# Sheet1.net
KiCad netlist of a schematic drawn in Altium Designer
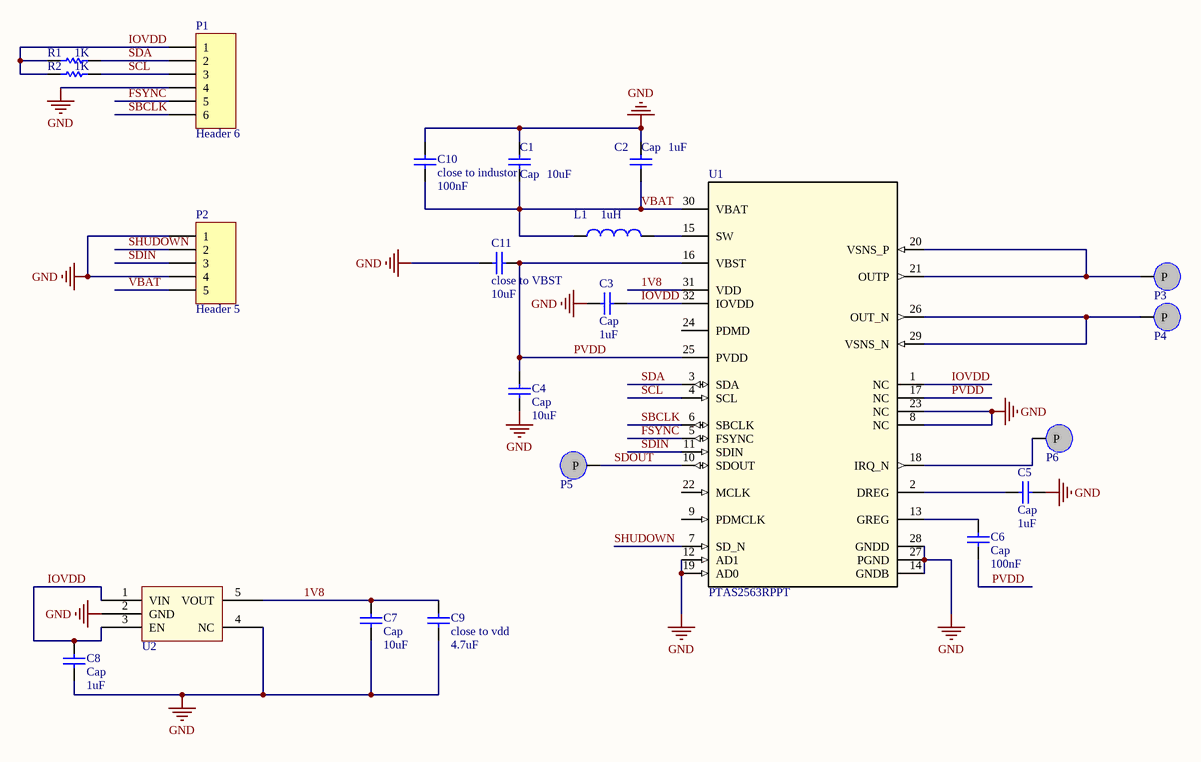
[diagram p0: Sheet1.SchDoc]

(export (version "E")
  (design (tool "Eeschema 10.0.6"))
  (components
    (comp (ref "C1")
      (value "Cap")
      (footprint "6-0805_L")
      (description "Capacitor")
      (fields (field (name "ALTIUM_VALUE") "10uF") (field (name "PUBLISHER") "Altium Limited"))
      (libsource (lib "Miscellaneous Devices") (part "Cap"))
    )
    (comp (ref "C2")
      (value "Cap")
      (footprint "6-0805_L")
      (description "Capacitor")
      (fields (field (name "ALTIUM_VALUE") "1uF") (field (name "PUBLISHER") "Altium Limited"))
      (libsource (lib "Miscellaneous Devices") (part "Cap"))
    )
    (comp (ref "C3")
      (value "Cap")
      (footprint "6-0805_L")
      (description "Capacitor")
      (fields (field (name "ALTIUM_VALUE") "1uF") (field (name "PUBLISHER") "Altium Limited"))
      (libsource (lib "Miscellaneous Devices") (part "Cap"))
    )
    (comp (ref "C4")
      (value "Cap")
      (footprint "6-0805_L")
      (description "Capacitor")
      (fields (field (name "ALTIUM_VALUE") "10uF") (field (name "PUBLISHER") "Altium Limited"))
      (libsource (lib "Miscellaneous Devices") (part "Cap"))
    )
    (comp (ref "C5")
      (value "Cap")
      (footprint "6-0805_L")
      (description "Capacitor")
      (fields (field (name "ALTIUM_VALUE") "1uF") (field (name "PUBLISHER") "Altium Limited"))
      (libsource (lib "Miscellaneous Devices") (part "Cap"))
    )
    (comp (ref "C6")
      (value "Cap")
      (footprint "1608[0603]")
      (description "Capacitor")
      (fields (field (name "ALTIUM_VALUE") "100nF") (field (name "PUBLISHER") "Altium Limited"))
      (libsource (lib "Miscellaneous Devices") (part "Cap"))
    )
    (comp (ref "C7")
      (value "Cap")
      (footprint "6-0805_L")
      (description "Capacitor")
      (fields (field (name "ALTIUM_VALUE") "10uF") (field (name "PUBLISHER") "Altium Limited"))
      (libsource (lib "Miscellaneous Devices") (part "Cap"))
    )
    (comp (ref "C8")
      (value "Cap")
      (footprint "6-0805_L")
      (description "Capacitor")
      (fields (field (name "ALTIUM_VALUE") "1uF") (field (name "PUBLISHER") "Altium Limited"))
      (libsource (lib "Miscellaneous Devices") (part "Cap"))
    )
    (comp (ref "C9")
      (value "close to vdd")
      (footprint "6-0805_L")
      (description "Capacitor")
      (fields (field (name "ALTIUM_VALUE") "4.7uF") (field (name "PUBLISHER") "Altium Limited"))
      (libsource (lib "Miscellaneous Devices") (part "Cap"))
    )
    (comp (ref "C10")
      (value "close to industor")
      (footprint "0402")
      (description "Capacitor")
      (fields (field (name "ALTIUM_VALUE") "100nF") (field (name "PUBLISHER") "Altium Limited"))
      (libsource (lib "Miscellaneous Devices") (part "Cap"))
    )
    (comp (ref "C11")
      (value "close to VBST")
      (footprint "6-0805_L")
      (description "Capacitor")
      (fields (field (name "ALTIUM_VALUE") "10uF") (field (name "PUBLISHER") "Altium Limited"))
      (libsource (lib "Miscellaneous Devices") (part "Cap"))
    )
    (comp (ref "L1")
      (value "1uH")
      (footprint "4040X20L")
      (description "Inductor")
      (fields (field (name "PUBLISHER") "Altium Limited"))
      (libsource (lib "Miscellaneous Devices") (part "Inductor"))
    )
    (comp (ref "P1")
      (value "Header 6")
      (footprint "DIP6-HOLE")
      (description "Header, 6-Pin")
      (fields (field (name "PUBLISHER") "Altium Limited"))
      (libsource (lib "Miscellaneous Connectors") (part "Header 6"))
    )
    (comp (ref "P2")
      (value "Header 5")
      (footprint "DIP5-HOLE")
      (description "Header, 5-Pin")
      (fields (field (name "PUBLISHER") "Altium Limited"))
      (libsource (lib "Miscellaneous Connectors") (part "Header 5"))
    )
    (comp (ref "P3") (value "Point") (footprint "Point") (libsource (lib "cl_sch") (part "Point")))
    (comp (ref "P4") (value "Point") (footprint "Point") (libsource (lib "cl_sch") (part "Point")))
    (comp (ref "P5") (value "Point") (footprint "Point-min") (libsource (lib "cl_sch") (part "Point")))
    (comp (ref "P6") (value "Point") (footprint "Point-min") (libsource (lib "cl_sch") (part "Point")))
    (comp (ref "R1")
      (value "1K")
      (footprint "0402")
      (description "Resistor")
      (fields (field (name "Comment") "Res1") (field (name "PUBLISHER") "Altium Limited"))
      (libsource (lib "Miscellaneous Devices") (part "Res1"))
    )
    (comp (ref "R2")
      (value "1K")
      (footprint "0402")
      (description "Resistor")
      (fields (field (name "Comment") "Res1") (field (name "PUBLISHER") "Altium Limited"))
      (libsource (lib "Miscellaneous Devices") (part "Res1"))
    )
    (comp (ref "U1")
      (value "PTAS2563RPPT")
      (footprint "RPP0032B-MFG")
      (description "No Description Available")
      (fields (field (name "COPYRIGHT") "Copyright (C) 2023 Ultra Librarian. All rights reserved."))
      (libsource (lib "PTAS2563RPPT") (part "PTAS2563RPPT"))
    )
    (comp (ref "U2") (value "TPS70918") (footprint "SOT23-5") (libsource (lib "cl_sch") (part "TPS70918")))
  )
  (nets
    (net (code "1") (name "/1V8") (class "Default")
      (node (ref "C7") (pin "2") (pinfunction "2_2") (pintype "passive"))
      (node (ref "C9") (pin "2") (pinfunction "2_2") (pintype "passive"))
      (node (ref "U1") (pin "31") (pinfunction "VDD_31") (pintype "power_in"))
      (node (ref "U2") (pin "5") (pinfunction "VOUT_5") (pintype "passive"))
    )
    (net (code "2") (name "/FSYNC") (class "Default")
      (node (ref "P1") (pin "5") (pinfunction "5_5") (pintype "passive"))
      (node (ref "U1") (pin "5") (pinfunction "FSYNC_5") (pintype "bidirectional"))
    )
    (net (code "3") (name "/IOVDD") (class "Default")
      (node (ref "C3") (pin "1") (pinfunction "1_1") (pintype "passive"))
      (node (ref "C8") (pin "2") (pinfunction "2_2") (pintype "passive"))
      (node (ref "P1") (pin "1") (pinfunction "1_1") (pintype "passive"))
      (node (ref "R1") (pin "1") (pinfunction "1_1") (pintype "passive"))
      (node (ref "R2") (pin "1") (pinfunction "1_1") (pintype "passive"))
      (node (ref "U1") (pin "1") (pinfunction "NC_1") (pintype "passive"))
      (node (ref "U1") (pin "32") (pinfunction "IOVDD_32") (pintype "power_in"))
      (node (ref "U2") (pin "1") (pinfunction "VIN_1") (pintype "passive"))
      (node (ref "U2") (pin "3") (pinfunction "EN_3") (pintype "passive"))
    )
    (net (code "4") (name "/PVDD") (class "Default")
      (node (ref "C11") (pin "1") (pinfunction "1_1") (pintype "passive"))
      (node (ref "C4") (pin "2") (pinfunction "2_2") (pintype "passive"))
      (node (ref "C6") (pin "2") (pinfunction "2_2") (pintype "passive"))
      (node (ref "U1") (pin "16") (pinfunction "VBST_16") (pintype "power_in"))
      (node (ref "U1") (pin "17") (pinfunction "NC_17") (pintype "passive"))
      (node (ref "U1") (pin "25") (pinfunction "PVDD_25") (pintype "power_in"))
    )
    (net (code "5") (name "/SBCLK") (class "Default")
      (node (ref "P1") (pin "6") (pinfunction "6_6") (pintype "passive"))
      (node (ref "U1") (pin "6") (pinfunction "SBCLK_6") (pintype "bidirectional"))
    )
    (net (code "6") (name "/SCL") (class "Default")
      (node (ref "P1") (pin "3") (pinfunction "3_3") (pintype "passive"))
      (node (ref "R2") (pin "2") (pinfunction "2_2") (pintype "passive"))
      (node (ref "U1") (pin "4") (pinfunction "SCL_4") (pintype "input"))
    )
    (net (code "7") (name "/SDA") (class "Default")
      (node (ref "P1") (pin "2") (pinfunction "2_2") (pintype "passive"))
      (node (ref "R1") (pin "2") (pinfunction "2_2") (pintype "passive"))
      (node (ref "U1") (pin "3") (pinfunction "SDA_3") (pintype "bidirectional"))
    )
    (net (code "8") (name "/SDIN") (class "Default")
      (node (ref "P2") (pin "3") (pinfunction "3_3") (pintype "passive"))
      (node (ref "U1") (pin "11") (pinfunction "SDIN_11") (pintype "input"))
    )
    (net (code "9") (name "/SDOUT") (class "Default")
      (node (ref "P5") (pin "1") (pinfunction "P_1") (pintype "passive"))
      (node (ref "U1") (pin "10") (pinfunction "SDOUT_10") (pintype "bidirectional"))
    )
    (net (code "10") (name "/SHUDOWN") (class "Default")
      (node (ref "P2") (pin "2") (pinfunction "2_2") (pintype "passive"))
      (node (ref "U1") (pin "7") (pinfunction "SD_N_7") (pintype "input"))
    )
    (net (code "11") (name "/VBAT") (class "Default")
      (node (ref "C1") (pin "2") (pinfunction "2_2") (pintype "passive"))
      (node (ref "C10") (pin "1") (pinfunction "1_1") (pintype "passive"))
      (node (ref "C2") (pin "1") (pinfunction "1_1") (pintype "passive"))
      (node (ref "L1") (pin "1") (pinfunction "1_1") (pintype "passive"))
      (node (ref "P2") (pin "5") (pinfunction "5_5") (pintype "passive"))
      (node (ref "U1") (pin "30") (pinfunction "VBAT_30") (pintype "power_in"))
    )
    (net (code "12") (name "GND") (class "Default")
      (node (ref "C1") (pin "1") (pinfunction "1_1") (pintype "passive"))
      (node (ref "C10") (pin "2") (pinfunction "2_2") (pintype "passive"))
      (node (ref "C11") (pin "2") (pinfunction "2_2") (pintype "passive"))
      (node (ref "C2") (pin "2") (pinfunction "2_2") (pintype "passive"))
      (node (ref "C3") (pin "2") (pinfunction "2_2") (pintype "passive"))
      (node (ref "C4") (pin "1") (pinfunction "1_1") (pintype "passive"))
      (node (ref "C5") (pin "1") (pinfunction "1_1") (pintype "passive"))
      (node (ref "C7") (pin "1") (pinfunction "1_1") (pintype "passive"))
      (node (ref "C8") (pin "1") (pinfunction "1_1") (pintype "passive"))
      (node (ref "C9") (pin "1") (pinfunction "1_1") (pintype "passive"))
      (node (ref "P1") (pin "4") (pinfunction "4_4") (pintype "passive"))
      (node (ref "P2") (pin "1") (pinfunction "1_1") (pintype "passive"))
      (node (ref "P2") (pin "4") (pinfunction "4_4") (pintype "passive"))
      (node (ref "U1") (pin "12") (pinfunction "AD1_12") (pintype "input"))
      (node (ref "U1") (pin "14") (pinfunction "GNDB_14") (pintype "power_in"))
      (node (ref "U1") (pin "19") (pinfunction "AD0_19") (pintype "input"))
      (node (ref "U1") (pin "23") (pinfunction "NC_23") (pintype "passive"))
      (node (ref "U1") (pin "27") (pinfunction "PGND_27") (pintype "power_in"))
      (node (ref "U1") (pin "28") (pinfunction "GNDD_28") (pintype "power_in"))
      (node (ref "U1") (pin "8") (pinfunction "NC_8") (pintype "passive"))
      (node (ref "U2") (pin "2") (pinfunction "GND_2") (pintype "passive"))
      (node (ref "U2") (pin "4") (pinfunction "NC_4") (pintype "passive"))
    )
    (net (code "13") (name "Net-(P3-P)") (class "Default")
      (node (ref "P3") (pin "1") (pinfunction "P_1") (pintype "passive"))
      (node (ref "U1") (pin "20") (pinfunction "VSNS_P_20") (pintype "input"))
      (node (ref "U1") (pin "21") (pinfunction "OUTP_21") (pintype "output"))
    )
    (net (code "14") (name "Net-(P4-P)") (class "Default")
      (node (ref "P4") (pin "1") (pinfunction "P_1") (pintype "passive"))
      (node (ref "U1") (pin "26") (pinfunction "OUT_N_26") (pintype "output"))
      (node (ref "U1") (pin "29") (pinfunction "VSNS_N_29") (pintype "input"))
    )
    (net (code "15") (name "Net-(P6-P)") (class "Default")
      (node (ref "P6") (pin "1") (pinfunction "P_1") (pintype "passive"))
      (node (ref "U1") (pin "18") (pinfunction "IRQ_N_18") (pintype "output"))
    )
    (net (code "16") (name "Net-(U1-DREG)") (class "Default")
      (node (ref "C5") (pin "2") (pinfunction "2_2") (pintype "passive"))
      (node (ref "U1") (pin "2") (pinfunction "DREG_2") (pintype "passive"))
    )
    (net (code "17") (name "Net-(U1-GREG)") (class "Default")
      (node (ref "C6") (pin "1") (pinfunction "1_1") (pintype "passive"))
      (node (ref "U1") (pin "13") (pinfunction "GREG_13") (pintype "passive"))
    )
    (net (code "18") (name "Net-(U1-SW)") (class "Default")
      (node (ref "L1") (pin "2") (pinfunction "2_2") (pintype "passive"))
      (node (ref "U1") (pin "15") (pinfunction "SW_15") (pintype "power_in"))
    )
    (net (code "19") (name "unconnected-(U1-MCLK-Pad22)") (class "Default")
      (node (ref "U1") (pin "22") (pinfunction "MCLK_22") (pintype "input"))
    )
    (net (code "20") (name "unconnected-(U1-PDMCLK-Pad9)") (class "Default")
      (node (ref "U1") (pin "9") (pinfunction "PDMCLK_9") (pintype "input"))
    )
    (net (code "21") (name "unconnected-(U1-PDMD-Pad24)") (class "Default")
      (node (ref "U1") (pin "24") (pinfunction "PDMD_24") (pintype "power_in"))
    )
  )
)
